# circuit_R1.net
KiCad netlist of a schematic drawn in EAGLE
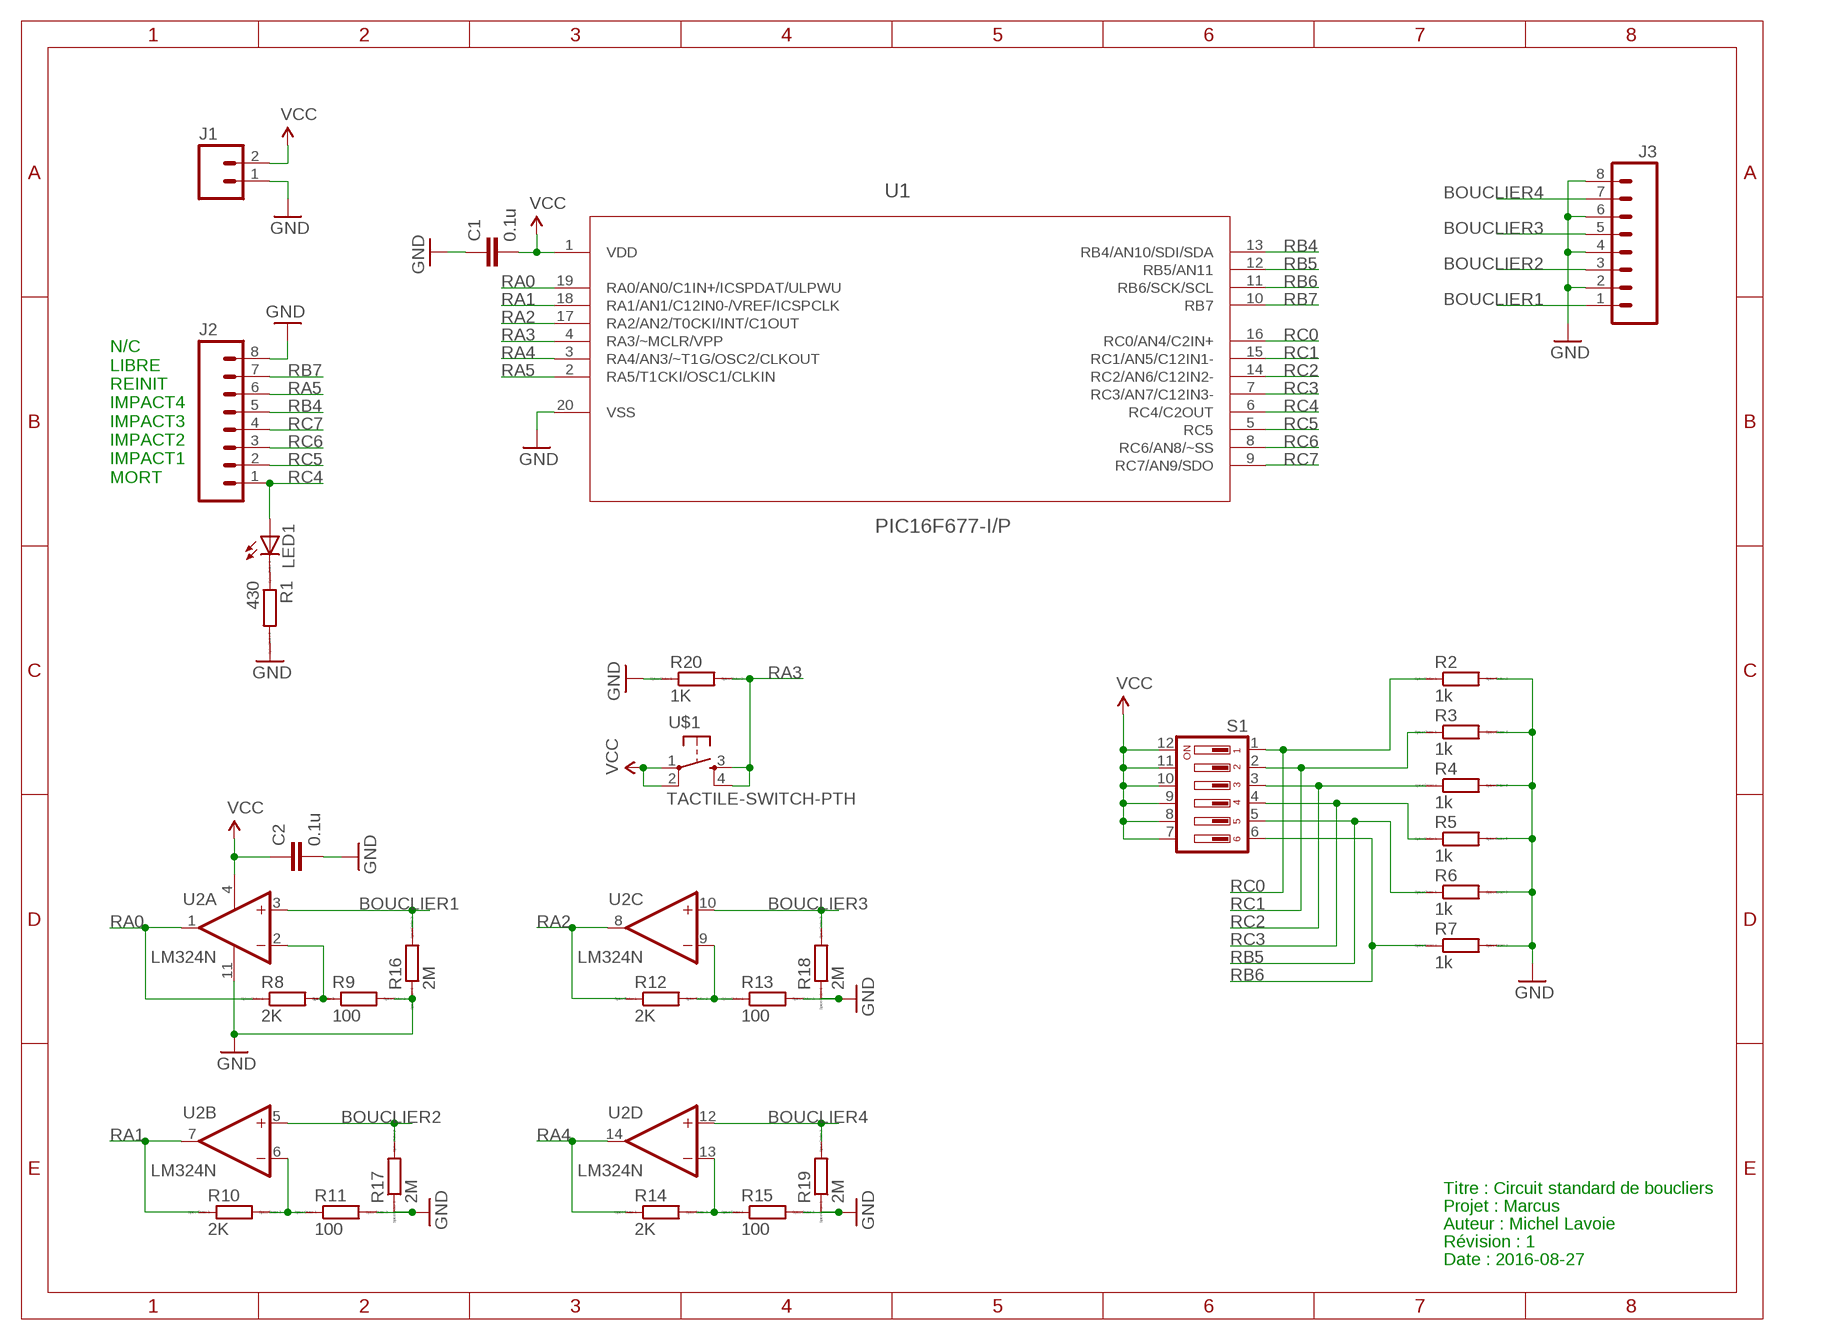
[diagram p0: schematic, sheet 1]

(export (version "E")
  (design (tool "Eeschema 10.0.6"))
  (components
    (comp (ref "C1")
      (value "0.1u")
      (footprint "eagle-import:CAP-PTH-SMALL")
      (libsource (lib "eagle-import") (part "CAPPTH"))
    )
    (comp (ref "C2")
      (value "0.1u")
      (footprint "eagle-import:CAP-PTH-SMALL")
      (libsource (lib "eagle-import") (part "CAPPTH"))
    )
    (comp (ref "J1")
      (value "M02PTH")
      (footprint "eagle-import:1X02")
      (libsource (lib "eagle-import") (part "M02PTH"))
    )
    (comp (ref "J2")
      (value "M08NO_SILK")
      (footprint "eagle-import:1X08_PIN1_NO_SILK")
      (libsource (lib "eagle-import") (part "M08NO_SILK"))
    )
    (comp (ref "J3")
      (value "M08NO_SILK")
      (footprint "eagle-import:1X08_PIN1_NO_SILK")
      (libsource (lib "eagle-import") (part "M08NO_SILK"))
    )
    (comp (ref "LED1")
      (value "LED3MM")
      (footprint "eagle-import:LED3MM")
      (libsource (lib "eagle-import") (part "LED3MM"))
    )
    (comp (ref "R1")
      (value "430")
      (footprint "eagle-import:0207_10")
      (libsource (lib "eagle-import") (part "R0207/10"))
    )
    (comp (ref "R2")
      (value "1k")
      (footprint "eagle-import:0207_10")
      (libsource (lib "eagle-import") (part "R0207/10"))
    )
    (comp (ref "R3")
      (value "1k")
      (footprint "eagle-import:0207_10")
      (libsource (lib "eagle-import") (part "R0207/10"))
    )
    (comp (ref "R4")
      (value "1k")
      (footprint "eagle-import:0207_10")
      (libsource (lib "eagle-import") (part "R0207/10"))
    )
    (comp (ref "R5")
      (value "1k")
      (footprint "eagle-import:0207_10")
      (libsource (lib "eagle-import") (part "R0207/10"))
    )
    (comp (ref "R6")
      (value "1k")
      (footprint "eagle-import:0207_10")
      (libsource (lib "eagle-import") (part "R0207/10"))
    )
    (comp (ref "R7")
      (value "1k")
      (footprint "eagle-import:0207_10")
      (libsource (lib "eagle-import") (part "R0207/10"))
    )
    (comp (ref "R8")
      (value "2K")
      (footprint "eagle-import:0207_10")
      (libsource (lib "eagle-import") (part "R0207/10"))
    )
    (comp (ref "R9")
      (value "100")
      (footprint "eagle-import:0207_10")
      (libsource (lib "eagle-import") (part "R0207/10"))
    )
    (comp (ref "R10")
      (value "2K")
      (footprint "eagle-import:0207_10")
      (libsource (lib "eagle-import") (part "R0207/10"))
    )
    (comp (ref "R11")
      (value "100")
      (footprint "eagle-import:0207_10")
      (libsource (lib "eagle-import") (part "R0207/10"))
    )
    (comp (ref "R12")
      (value "2K")
      (footprint "eagle-import:0207_10")
      (libsource (lib "eagle-import") (part "R0207/10"))
    )
    (comp (ref "R13")
      (value "100")
      (footprint "eagle-import:0207_10")
      (libsource (lib "eagle-import") (part "R0207/10"))
    )
    (comp (ref "R14")
      (value "2K")
      (footprint "eagle-import:0207_10")
      (libsource (lib "eagle-import") (part "R0207/10"))
    )
    (comp (ref "R15")
      (value "100")
      (footprint "eagle-import:0207_10")
      (libsource (lib "eagle-import") (part "R0207/10"))
    )
    (comp (ref "R16")
      (value "2M")
      (footprint "eagle-import:0207_10")
      (libsource (lib "eagle-import") (part "R0207/10"))
    )
    (comp (ref "R17")
      (value "2M")
      (footprint "eagle-import:0207_10")
      (libsource (lib "eagle-import") (part "R0207/10"))
    )
    (comp (ref "R18")
      (value "2M")
      (footprint "eagle-import:0207_10")
      (libsource (lib "eagle-import") (part "R0207/10"))
    )
    (comp (ref "R19")
      (value "2M")
      (footprint "eagle-import:0207_10")
      (libsource (lib "eagle-import") (part "R0207/10"))
    )
    (comp (ref "R20")
      (value "1K")
      (footprint "eagle-import:0207_10")
      (libsource (lib "eagle-import") (part "R0207/10"))
    )
    (comp (ref "S1")
      (value "DIP06YL")
      (footprint "eagle-import:DIP06YL")
      (libsource (lib "eagle-import") (part "DIP06YL"))
    )
    (comp (ref "U$1")
      (value "TACTILE-SWITCH-PTH")
      (footprint "eagle-import:TAC-SWITCH-PTH")
      (libsource (lib "eagle-import") (part "TACTILE-SWITCH-PTH"))
    )
    (comp (ref "U1")
      (value "PIC16F677-I/P")
      (footprint "eagle-import:DIP254P762X533-20")
      (libsource (lib "eagle-import") (part "PIC16F677-I/P"))
    )
    (comp (ref "U2")
      (value "LM324N")
      (footprint "eagle-import:DIL14")
      (libsource (lib "eagle-import") (part "LM324N"))
    )
  )
  (nets
    (net (code "1") (name "/BOUCLIER1") (class "Default")
      (node (ref "J3") (pin "1") (pinfunction "1_1") (pintype "passive"))
      (node (ref "R16") (pin "2") (pinfunction "2_2") (pintype "passive"))
      (node (ref "U2") (pin "3") (pinfunction "+IN_3") (pintype "input"))
    )
    (net (code "2") (name "/BOUCLIER2") (class "Default")
      (node (ref "J3") (pin "3") (pinfunction "3_3") (pintype "passive"))
      (node (ref "R17") (pin "2") (pinfunction "2_2") (pintype "passive"))
      (node (ref "U2") (pin "5") (pinfunction "+IN_5") (pintype "input"))
    )
    (net (code "3") (name "/BOUCLIER3") (class "Default")
      (node (ref "J3") (pin "5") (pinfunction "5_5") (pintype "passive"))
      (node (ref "R18") (pin "2") (pinfunction "2_2") (pintype "passive"))
      (node (ref "U2") (pin "10") (pinfunction "+IN_10") (pintype "input"))
    )
    (net (code "4") (name "/BOUCLIER4") (class "Default")
      (node (ref "J3") (pin "7") (pinfunction "7_7") (pintype "passive"))
      (node (ref "R19") (pin "2") (pinfunction "2_2") (pintype "passive"))
      (node (ref "U2") (pin "12") (pinfunction "+IN_12") (pintype "input"))
    )
    (net (code "5") (name "/RA0") (class "Default")
      (node (ref "R8") (pin "1") (pinfunction "1_1") (pintype "passive"))
      (node (ref "U1") (pin "19") (pinfunction "RA0/AN0/C1IN+/ICSPDAT/ULPWU_19") (pintype "bidirectional"))
      (node (ref "U2") (pin "1") (pinfunction "OUT_1") (pintype "output"))
    )
    (net (code "6") (name "/RA1") (class "Default")
      (node (ref "R10") (pin "1") (pinfunction "1_1") (pintype "passive"))
      (node (ref "U1") (pin "18") (pinfunction "RA1/AN1/C12IN0-/VREF/ICSPCLK_18") (pintype "bidirectional"))
      (node (ref "U2") (pin "7") (pinfunction "OUT_7") (pintype "output"))
    )
    (net (code "7") (name "/RA2") (class "Default")
      (node (ref "R12") (pin "1") (pinfunction "1_1") (pintype "passive"))
      (node (ref "U1") (pin "17") (pinfunction "RA2/AN2/T0CKI/INT/C1OUT_17") (pintype "bidirectional"))
      (node (ref "U2") (pin "8") (pinfunction "OUT_8") (pintype "output"))
    )
    (net (code "8") (name "/RA3") (class "Default")
      (node (ref "R20") (pin "2") (pinfunction "2_2") (pintype "passive"))
      (node (ref "U$1") (pin "3") (pinfunction "3_3") (pintype "passive"))
      (node (ref "U$1") (pin "4") (pinfunction "4_4") (pintype "passive"))
      (node (ref "U1") (pin "4") (pinfunction "RA3/~{MCLR/VPP}_4") (pintype "bidirectional"))
    )
    (net (code "9") (name "/RA4") (class "Default")
      (node (ref "R14") (pin "1") (pinfunction "1_1") (pintype "passive"))
      (node (ref "U1") (pin "3") (pinfunction "RA4/AN3/~{T1G/OSC2/CLKOUT}_3") (pintype "bidirectional"))
      (node (ref "U2") (pin "14") (pinfunction "OUT_14") (pintype "output"))
    )
    (net (code "10") (name "/RA5") (class "Default")
      (node (ref "J2") (pin "6") (pinfunction "6_6") (pintype "passive"))
      (node (ref "U1") (pin "2") (pinfunction "RA5/T1CKI/OSC1/CLKIN_2") (pintype "bidirectional"))
    )
    (net (code "11") (name "/RB4") (class "Default")
      (node (ref "J2") (pin "5") (pinfunction "5_5") (pintype "passive"))
      (node (ref "U1") (pin "13") (pinfunction "RB4/AN10/SDI/SDA_13") (pintype "bidirectional"))
    )
    (net (code "12") (name "/RB5") (class "Default")
      (node (ref "R6") (pin "1") (pinfunction "1_1") (pintype "passive"))
      (node (ref "S1") (pin "5") (pinfunction "5_5") (pintype "passive"))
      (node (ref "U1") (pin "12") (pinfunction "RB5/AN11_12") (pintype "bidirectional"))
    )
    (net (code "13") (name "/RB6") (class "Default")
      (node (ref "R7") (pin "1") (pinfunction "1_1") (pintype "passive"))
      (node (ref "S1") (pin "6") (pinfunction "6_6") (pintype "passive"))
      (node (ref "U1") (pin "11") (pinfunction "RB6/SCK/SCL_11") (pintype "bidirectional"))
    )
    (net (code "14") (name "/RB7") (class "Default")
      (node (ref "J2") (pin "7") (pinfunction "7_7") (pintype "passive"))
      (node (ref "U1") (pin "10") (pinfunction "RB7_10") (pintype "bidirectional"))
    )
    (net (code "15") (name "/RC0") (class "Default")
      (node (ref "R2") (pin "1") (pinfunction "1_1") (pintype "passive"))
      (node (ref "S1") (pin "1") (pinfunction "1_1") (pintype "passive"))
      (node (ref "U1") (pin "16") (pinfunction "RC0/AN4/C2IN+_16") (pintype "bidirectional"))
    )
    (net (code "16") (name "/RC1") (class "Default")
      (node (ref "R3") (pin "1") (pinfunction "1_1") (pintype "passive"))
      (node (ref "S1") (pin "2") (pinfunction "2_2") (pintype "passive"))
      (node (ref "U1") (pin "15") (pinfunction "RC1/AN5/C12IN1-_15") (pintype "bidirectional"))
    )
    (net (code "17") (name "/RC2") (class "Default")
      (node (ref "R4") (pin "1") (pinfunction "1_1") (pintype "passive"))
      (node (ref "S1") (pin "3") (pinfunction "3_3") (pintype "passive"))
      (node (ref "U1") (pin "14") (pinfunction "RC2/AN6/C12IN2-_14") (pintype "bidirectional"))
    )
    (net (code "18") (name "/RC3") (class "Default")
      (node (ref "R5") (pin "1") (pinfunction "1_1") (pintype "passive"))
      (node (ref "S1") (pin "4") (pinfunction "4_4") (pintype "passive"))
      (node (ref "U1") (pin "7") (pinfunction "RC3/AN7/C12IN3-_7") (pintype "bidirectional"))
    )
    (net (code "19") (name "/RC4") (class "Default")
      (node (ref "J2") (pin "1") (pinfunction "1_1") (pintype "passive"))
      (node (ref "LED1") (pin "A") (pinfunction "A_A") (pintype "passive"))
      (node (ref "U1") (pin "6") (pinfunction "RC4/C2OUT_6") (pintype "bidirectional"))
    )
    (net (code "20") (name "/RC5") (class "Default")
      (node (ref "J2") (pin "2") (pinfunction "2_2") (pintype "passive"))
      (node (ref "U1") (pin "5") (pinfunction "RC5_5") (pintype "bidirectional"))
    )
    (net (code "21") (name "/RC6") (class "Default")
      (node (ref "J2") (pin "3") (pinfunction "3_3") (pintype "passive"))
      (node (ref "U1") (pin "8") (pinfunction "RC6/AN8/~{SS}_8") (pintype "bidirectional"))
    )
    (net (code "22") (name "/RC7") (class "Default")
      (node (ref "J2") (pin "4") (pinfunction "4_4") (pintype "passive"))
      (node (ref "U1") (pin "9") (pinfunction "RC7/AN9/SDO_9") (pintype "bidirectional"))
    )
    (net (code "23") (name "GND") (class "Default")
      (node (ref "C1") (pin "1") (pinfunction "1_1") (pintype "passive"))
      (node (ref "C2") (pin "2") (pinfunction "2_2") (pintype "passive"))
      (node (ref "J1") (pin "1") (pinfunction "1_1") (pintype "passive"))
      (node (ref "J2") (pin "8") (pinfunction "8_8") (pintype "passive"))
      (node (ref "J3") (pin "2") (pinfunction "2_2") (pintype "passive"))
      (node (ref "J3") (pin "4") (pinfunction "4_4") (pintype "passive"))
      (node (ref "J3") (pin "6") (pinfunction "6_6") (pintype "passive"))
      (node (ref "J3") (pin "8") (pinfunction "8_8") (pintype "passive"))
      (node (ref "R1") (pin "2") (pinfunction "2_2") (pintype "passive"))
      (node (ref "R11") (pin "2") (pinfunction "2_2") (pintype "passive"))
      (node (ref "R13") (pin "2") (pinfunction "2_2") (pintype "passive"))
      (node (ref "R15") (pin "2") (pinfunction "2_2") (pintype "passive"))
      (node (ref "R16") (pin "1") (pinfunction "1_1") (pintype "passive"))
      (node (ref "R17") (pin "1") (pinfunction "1_1") (pintype "passive"))
      (node (ref "R18") (pin "1") (pinfunction "1_1") (pintype "passive"))
      (node (ref "R19") (pin "1") (pinfunction "1_1") (pintype "passive"))
      (node (ref "R2") (pin "2") (pinfunction "2_2") (pintype "passive"))
      (node (ref "R20") (pin "1") (pinfunction "1_1") (pintype "passive"))
      (node (ref "R3") (pin "2") (pinfunction "2_2") (pintype "passive"))
      (node (ref "R4") (pin "2") (pinfunction "2_2") (pintype "passive"))
      (node (ref "R5") (pin "2") (pinfunction "2_2") (pintype "passive"))
      (node (ref "R6") (pin "2") (pinfunction "2_2") (pintype "passive"))
      (node (ref "R7") (pin "2") (pinfunction "2_2") (pintype "passive"))
      (node (ref "R9") (pin "2") (pinfunction "2_2") (pintype "passive"))
      (node (ref "U1") (pin "20") (pinfunction "VSS_20") (pintype "power_in"))
      (node (ref "U2") (pin "11") (pinfunction "V-_11") (pintype "power_in"))
    )
    (net (code "24") (name "Net-(LED1-C)") (class "Default")
      (node (ref "LED1") (pin "K") (pinfunction "C_K") (pintype "passive"))
      (node (ref "R1") (pin "1") (pinfunction "1_1") (pintype "passive"))
    )
    (net (code "25") (name "Net-(U2A--IN)") (class "Default")
      (node (ref "R8") (pin "2") (pinfunction "2_2") (pintype "passive"))
      (node (ref "R9") (pin "1") (pinfunction "1_1") (pintype "passive"))
      (node (ref "U2") (pin "2") (pinfunction "-IN_2") (pintype "input"))
    )
    (net (code "26") (name "Net-(U2B--IN)") (class "Default")
      (node (ref "R10") (pin "2") (pinfunction "2_2") (pintype "passive"))
      (node (ref "R11") (pin "1") (pinfunction "1_1") (pintype "passive"))
      (node (ref "U2") (pin "6") (pinfunction "-IN_6") (pintype "input"))
    )
    (net (code "27") (name "Net-(U2C--IN)") (class "Default")
      (node (ref "R12") (pin "2") (pinfunction "2_2") (pintype "passive"))
      (node (ref "R13") (pin "1") (pinfunction "1_1") (pintype "passive"))
      (node (ref "U2") (pin "9") (pinfunction "-IN_9") (pintype "input"))
    )
    (net (code "28") (name "Net-(U2D--IN)") (class "Default")
      (node (ref "R14") (pin "2") (pinfunction "2_2") (pintype "passive"))
      (node (ref "R15") (pin "1") (pinfunction "1_1") (pintype "passive"))
      (node (ref "U2") (pin "13") (pinfunction "-IN_13") (pintype "input"))
    )
    (net (code "29") (name "VCC") (class "Default")
      (node (ref "C1") (pin "2") (pinfunction "2_2") (pintype "passive"))
      (node (ref "C2") (pin "1") (pinfunction "1_1") (pintype "passive"))
      (node (ref "J1") (pin "2") (pinfunction "2_2") (pintype "passive"))
      (node (ref "S1") (pin "10") (pinfunction "10_10") (pintype "passive"))
      (node (ref "S1") (pin "11") (pinfunction "11_11") (pintype "passive"))
      (node (ref "S1") (pin "12") (pinfunction "12_12") (pintype "passive"))
      (node (ref "S1") (pin "7") (pinfunction "7_7") (pintype "passive"))
      (node (ref "S1") (pin "8") (pinfunction "8_8") (pintype "passive"))
      (node (ref "S1") (pin "9") (pinfunction "9_9") (pintype "passive"))
      (node (ref "U$1") (pin "1") (pinfunction "1_1") (pintype "passive"))
      (node (ref "U$1") (pin "2") (pinfunction "2_2") (pintype "passive"))
      (node (ref "U1") (pin "1") (pinfunction "VDD_1") (pintype "power_in"))
      (node (ref "U2") (pin "4") (pinfunction "V+_4") (pintype "power_in"))
    )
  )
)
